# IQ_modulator.net
KiCad netlist of a schematic drawn in Altium Designer
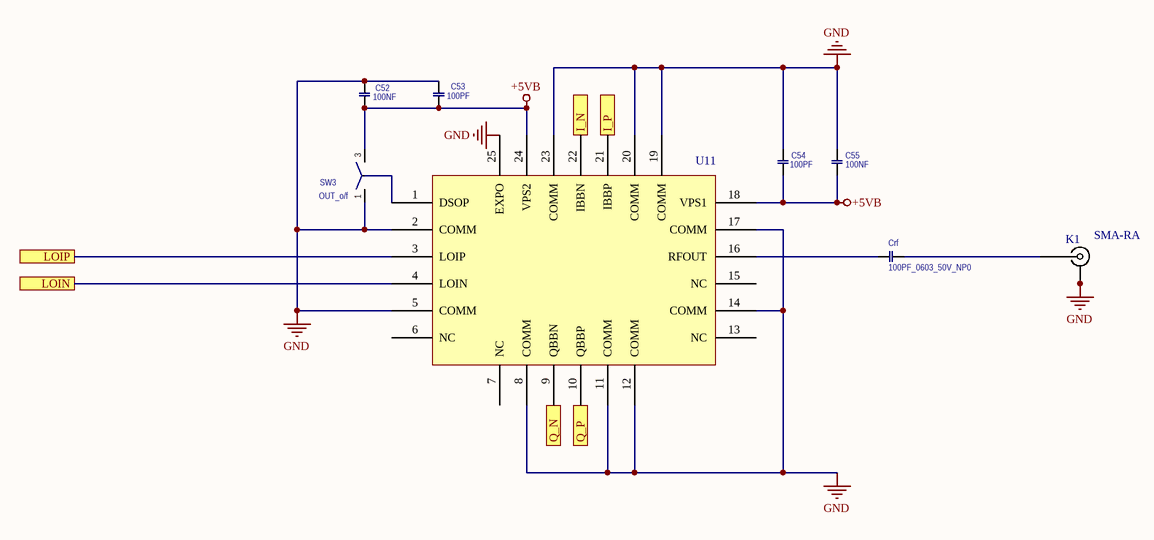
[diagram p0: IQ_modulator.SchDoc]

(export (version "E")
  (design (tool "Eeschema 10.0.6"))
  (components
    (comp (ref "C52")
      (value "100NF")
      (footprint "CAP0603")
      (description "128-8255    Capacitor MLC-X7R_0603_100NF_10%_50V; C0603C104K5RAC; KEMET; RoHS=Yes")
      (libsource (lib "ONEMULA_V2") (part "100NF_0603_50V_X7R"))
    )
    (comp (ref "C53")
      (value "100PF")
      (footprint "CAP0603")
      (description "141-4603    Capacitor MLC-NPO_0603_100PF_5%_50V; C0603C101J5GAC; KEMET; RoHS=Yes")
      (libsource (lib "ONEMULA_V2") (part "100PF_0603_50V_NP0"))
    )
    (comp (ref "C54")
      (value "100PF")
      (footprint "CAP0603")
      (description "141-4603    Capacitor MLC-NPO_0603_100PF_5%_50V; C0603C101J5GAC; KEMET; RoHS=Yes")
      (libsource (lib "ONEMULA_V2") (part "100PF_0603_50V_NP0"))
    )
    (comp (ref "C55")
      (value "100NF")
      (footprint "CAP0603")
      (description "128-8255    Capacitor MLC-X7R_0603_100NF_10%_50V; C0603C104K5RAC; KEMET; RoHS=Yes")
      (libsource (lib "ONEMULA_V2") (part "100NF_0603_50V_X7R"))
    )
    (comp (ref "Crf")
      (value "100PF_0603_50V_NP0")
      (footprint "CAP0603")
      (description "141-4603    Capacitor MLC-NPO_0603_100PF_5%_50V; C0603C101J5GAC; KEMET; RoHS=Yes")
      (libsource (lib "ONEMULA_V2") (part "100PF_0603_50V_NP0"))
    )
    (comp (ref "K1")
      (value "SMA-RA")
      (footprint "SMA-RA")
      (description "SMA THREADED RF CONNECTOR VERTICAL")
      (libsource (lib "vh_altium_library") (part "SMA-RA"))
    )
    (comp (ref "SW3")
      (value "OUT_o/f")
      (footprint "X3APH-SLIDER")
      (description "674-345     SWITCH SLIDE SPDT VERT; 09-03290-01; EAO; RoHS=Yes")
      (libsource (lib "*") (part "SLIDER3_TH_1"))
    )
    (comp (ref "U11") (value "ADL5375") (footprint "LFCSP") (libsource (lib "My_library") (part "ADL5375")))
  )
  (nets
    (net (code "1") (name "+5VB") (class "Default")
      (node (ref "C52") (pin "2") (pinfunction "2_2") (pintype "passive"))
      (node (ref "C53") (pin "2") (pinfunction "2_2") (pintype "passive"))
      (node (ref "C54") (pin "2") (pinfunction "2_2") (pintype "passive"))
      (node (ref "C55") (pin "2") (pinfunction "2_2") (pintype "passive"))
      (node (ref "SW3") (pin "3") (pinfunction "3_3") (pintype "passive"))
      (node (ref "U11") (pin "18") (pinfunction "VPS1_18") (pintype "passive"))
      (node (ref "U11") (pin "24") (pinfunction "VPS2_24") (pintype "passive"))
    )
    (net (code "2") (name "/I_N") (class "Default")
      (node (ref "U11") (pin "22") (pinfunction "IBBN_22") (pintype "passive"))
    )
    (net (code "3") (name "/I_P") (class "Default")
      (node (ref "U11") (pin "21") (pinfunction "IBBP_21") (pintype "passive"))
    )
    (net (code "4") (name "/LOIN") (class "Default")
      (node (ref "U11") (pin "4") (pinfunction "LOIN_4") (pintype "passive"))
    )
    (net (code "5") (name "/LOIP") (class "Default")
      (node (ref "U11") (pin "3") (pinfunction "LOIP_3") (pintype "passive"))
    )
    (net (code "6") (name "/Q_N") (class "Default")
      (node (ref "U11") (pin "9") (pinfunction "QBBN_9") (pintype "passive"))
    )
    (net (code "7") (name "/Q_P") (class "Default")
      (node (ref "U11") (pin "10") (pinfunction "QBBP_10") (pintype "passive"))
    )
    (net (code "8") (name "GND") (class "Default")
      (node (ref "C52") (pin "1") (pinfunction "1_1") (pintype "passive"))
      (node (ref "C53") (pin "1") (pinfunction "1_1") (pintype "passive"))
      (node (ref "C54") (pin "1") (pinfunction "1_1") (pintype "passive"))
      (node (ref "C55") (pin "1") (pinfunction "1_1") (pintype "passive"))
      (node (ref "K1") (pin "2") (pinfunction "2_2") (pintype "passive"))
      (node (ref "K1") (pin "3") (pinfunction "3_3") (pintype "passive"))
      (node (ref "K1") (pin "4") (pinfunction "4_4") (pintype "passive"))
      (node (ref "K1") (pin "5") (pinfunction "5_5") (pintype "passive"))
      (node (ref "SW3") (pin "1") (pinfunction "1_1") (pintype "passive"))
      (node (ref "U11") (pin "11") (pinfunction "COMM_11") (pintype "passive"))
      (node (ref "U11") (pin "12") (pinfunction "COMM_12") (pintype "passive"))
      (node (ref "U11") (pin "14") (pinfunction "COMM_14") (pintype "passive"))
      (node (ref "U11") (pin "17") (pinfunction "COMM_17") (pintype "passive"))
      (node (ref "U11") (pin "19") (pinfunction "COMM_19") (pintype "passive"))
      (node (ref "U11") (pin "2") (pinfunction "COMM_2") (pintype "passive"))
      (node (ref "U11") (pin "20") (pinfunction "COMM_20") (pintype "passive"))
      (node (ref "U11") (pin "23") (pinfunction "COMM_23") (pintype "passive"))
      (node (ref "U11") (pin "25") (pinfunction "EXPO_25") (pintype "passive"))
      (node (ref "U11") (pin "5") (pinfunction "COMM_5") (pintype "passive"))
      (node (ref "U11") (pin "8") (pinfunction "COMM_8") (pintype "passive"))
    )
    (net (code "9") (name "Net-(Crf-Pad2)") (class "Default")
      (node (ref "Crf") (pin "2") (pinfunction "2_2") (pintype "passive"))
      (node (ref "K1") (pin "1") (pinfunction "1_1") (pintype "passive"))
    )
    (net (code "10") (name "Net-(U11-DSOP)") (class "Default")
      (node (ref "SW3") (pin "2") (pinfunction "2_2") (pintype "passive"))
      (node (ref "U11") (pin "1") (pinfunction "DSOP_1") (pintype "passive"))
    )
    (net (code "11") (name "Net-(U11-RFOUT)") (class "Default")
      (node (ref "Crf") (pin "1") (pinfunction "1_1") (pintype "passive"))
      (node (ref "U11") (pin "16") (pinfunction "RFOUT_16") (pintype "passive"))
    )
    (net (code "12") (name "unconnected-(U11-NC-Pad6)") (class "Default")
      (node (ref "U11") (pin "6") (pinfunction "NC_6") (pintype "passive"))
    )
    (net (code "13") (name "unconnected-(U11-NC-Pad7)") (class "Default")
      (node (ref "U11") (pin "7") (pinfunction "NC_7") (pintype "passive"))
    )
    (net (code "14") (name "unconnected-(U11-NC-Pad13)") (class "Default")
      (node (ref "U11") (pin "13") (pinfunction "NC_13") (pintype "passive"))
    )
    (net (code "15") (name "unconnected-(U11-NC-Pad15)") (class "Default")
      (node (ref "U11") (pin "15") (pinfunction "NC_15") (pintype "passive"))
    )
  )
)
